# ScanseSweep_Final.net
KiCad netlist of a schematic drawn in EAGLE
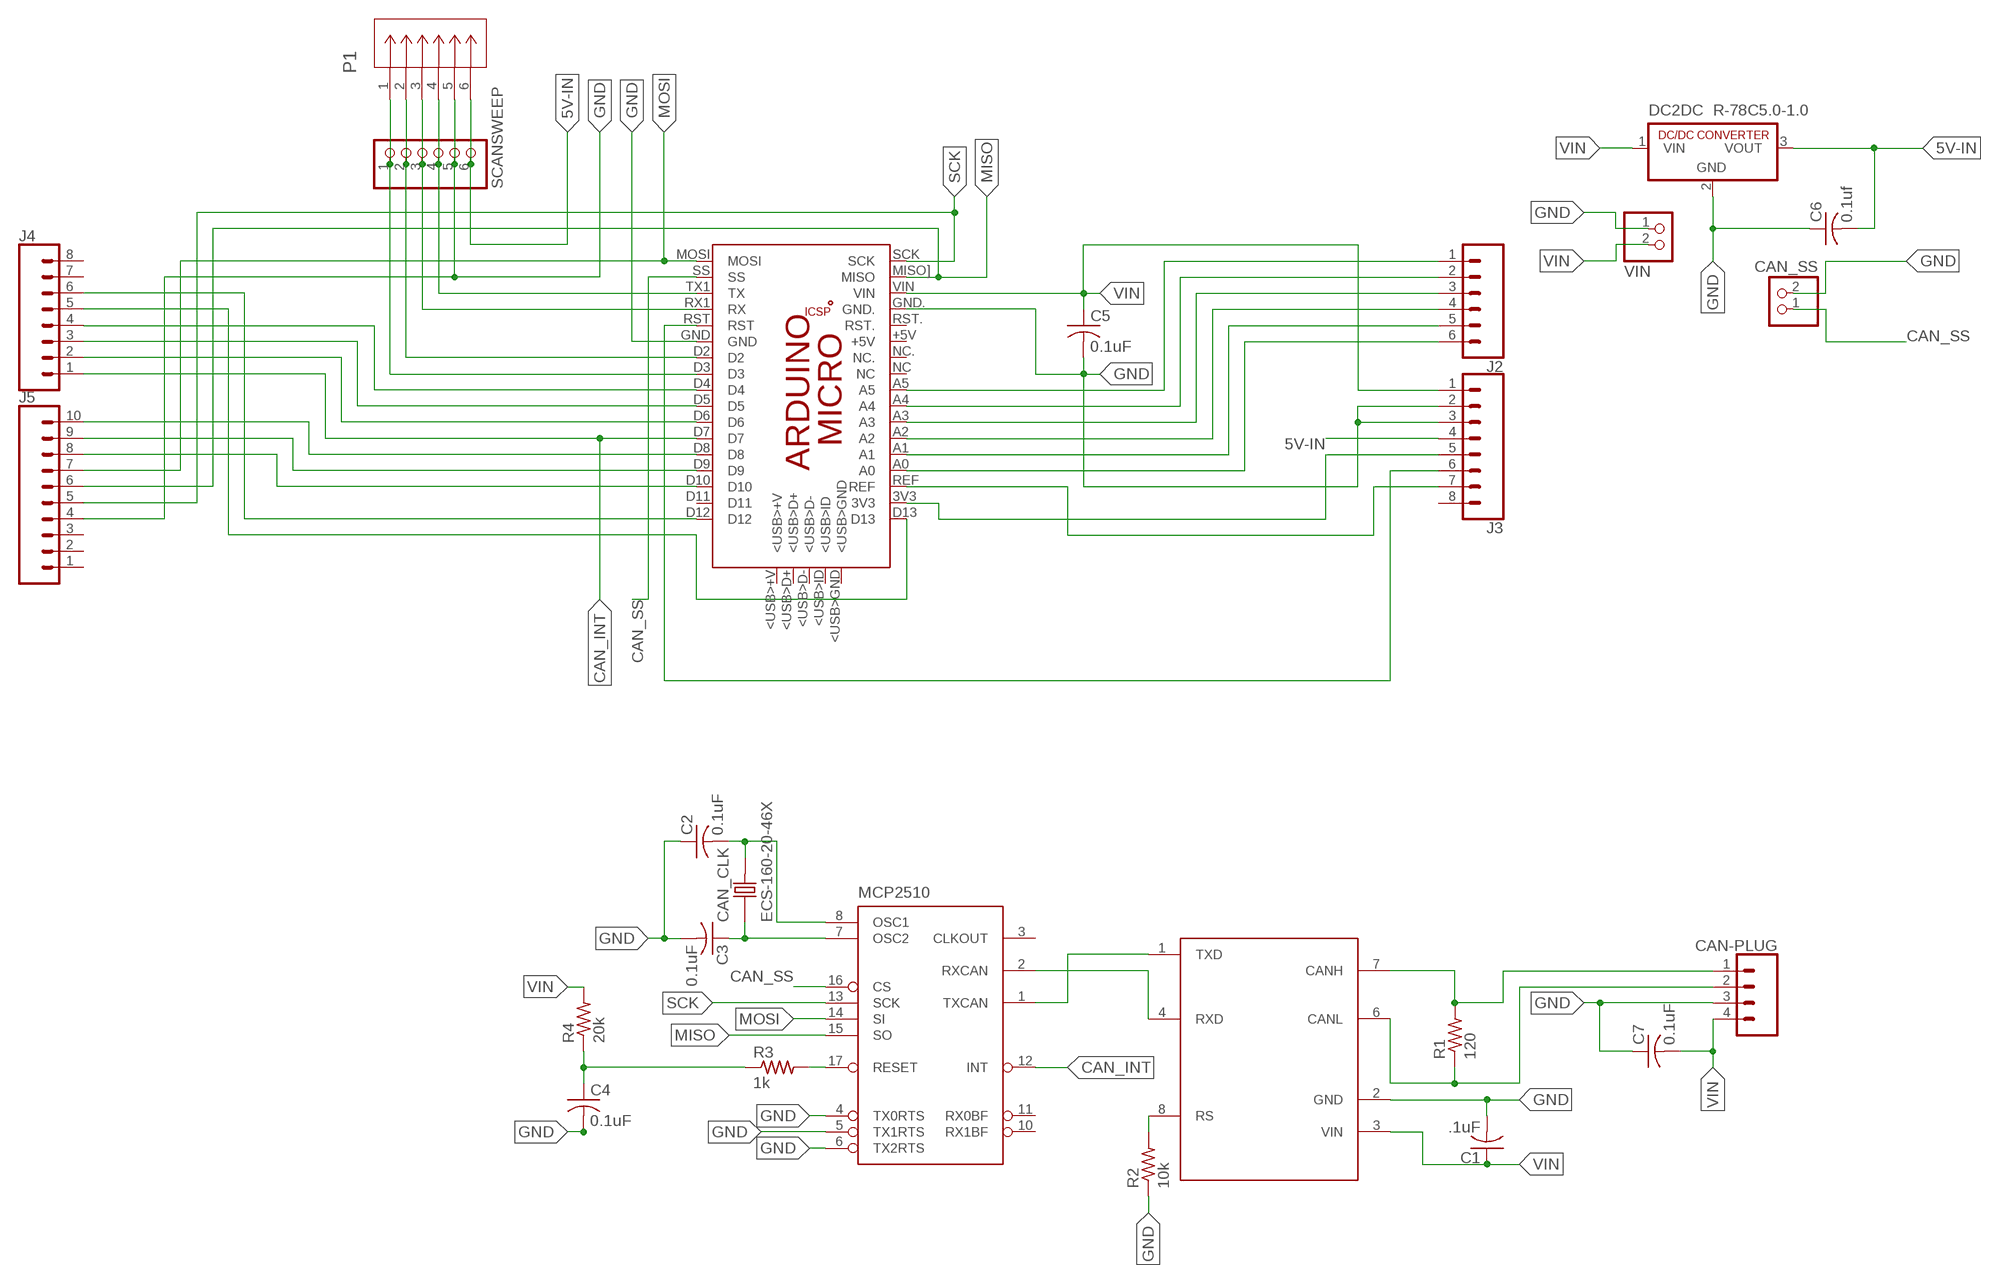
[diagram p0: schematic, sheet 1]

(export (version "E")
  (design (tool "Eeschema 10.0.6"))
  (components
    (comp (ref "C1")
      (value ".1uF")
      (footprint "eagle-import:C025-024X044")
      (libsource (lib "eagle-import") (part "C-US025-024X044"))
    )
    (comp (ref "C2")
      (value "0.1uF")
      (footprint "eagle-import:C025-024X044")
      (libsource (lib "eagle-import") (part "C-US025-024X044"))
    )
    (comp (ref "C3")
      (value "0.1uF")
      (footprint "eagle-import:C025-024X044")
      (libsource (lib "eagle-import") (part "C-US025-024X044"))
    )
    (comp (ref "C4")
      (value "0.1uF")
      (footprint "eagle-import:C025-024X044")
      (libsource (lib "eagle-import") (part "C-US025-024X044"))
    )
    (comp (ref "C5")
      (value "0.1uF")
      (footprint "eagle-import:C025-024X044")
      (libsource (lib "eagle-import") (part "C-US025-024X044"))
    )
    (comp (ref "C6")
      (value "0.1uf")
      (footprint "eagle-import:C025-024X044")
      (libsource (lib "eagle-import") (part "C-US025-024X044"))
    )
    (comp (ref "C7")
      (value "0.1uF")
      (footprint "eagle-import:C025-024X044")
      (libsource (lib "eagle-import") (part "C-US025-024X044"))
    )
    (comp (ref "CAN_CLK")
      (value "ECS-160-20-46X")
      (footprint "eagle-import:XTAL_ECS-160-20-46X")
      (fields (field (name "DIGI-KEY_PART_NUMBER") "XC1759-ND") (field (name "MF") "ECS Inc."))
      (libsource (lib "eagle-import") (part "ECS-160-20-46X"))
    )
    (comp (ref "CAN_SS_TEST")
      (value "CAN_SS")
      (footprint "eagle-import:1X02")
      (libsource (lib "eagle-import") (part "PINHD-1X2"))
    )
    (comp (ref "DC2DC")
      (value "R-78C5.0-1.0")
      (footprint "eagle-import:SIP3")
      (libsource (lib "eagle-import") (part "R-78C-1.05.0"))
    )
    (comp (ref "J1")
      (value "CAN-PLUG")
      (footprint "eagle-import:SCREWTERMINAL-3.5MM-4")
      (libsource (lib "eagle-import") (part "CONN_04SCREW"))
    )
    (comp (ref "J2")
      (value "CONN_06SILK_FEMALE_PTH")
      (footprint "eagle-import:1X06")
      (libsource (lib "eagle-import") (part "CONN_06SILK_FEMALE_PTH"))
    )
    (comp (ref "J3")
      (value "CONN_08\"")
      (footprint "eagle-import:1X08")
      (libsource (lib "eagle-import") (part "CONN_08{dblquote}"))
    )
    (comp (ref "J4")
      (value "CONN_08\"")
      (footprint "eagle-import:1X08")
      (libsource (lib "eagle-import") (part "CONN_08{dblquote}"))
    )
    (comp (ref "J5")
      (value "CONN_10\"")
      (footprint "eagle-import:1X10")
      (libsource (lib "eagle-import") (part "CONN_10{dblquote}"))
    )
    (comp (ref "MCP2510")
      (value "MCP2510P")
      (footprint "eagle-import:DIL18")
      (libsource (lib "eagle-import") (part "MCP2510P"))
    )
    (comp (ref "MCP2551")
      (value "MCP2551MCP2551")
      (footprint "eagle-import:DIL08")
      (libsource (lib "eagle-import") (part "MCP2551MCP2551"))
    )
    (comp (ref "P1")
      (value "S6B-ZR(LF)(SN)")
      (footprint "eagle-import:S6B-ZR")
      (fields (field (name "MANUFACTURER_PART_NUMBER") "S6BZRLFSN"))
      (libsource (lib "eagle-import") (part "S6B-ZR(LF)(SN)"))
    )
    (comp (ref "PCB2")
      (value "ARDUINO_MICRO")
      (footprint "eagle-import:ARDUINO_MICRO")
      (libsource (lib "eagle-import") (part "ARDUINO_MICRO"))
    )
    (comp (ref "R1")
      (value "120")
      (footprint "eagle-import:0204_5")
      (libsource (lib "eagle-import") (part "R-US_0204/5"))
    )
    (comp (ref "R2")
      (value "10k")
      (footprint "eagle-import:0204_5")
      (libsource (lib "eagle-import") (part "R-US_0204/5"))
    )
    (comp (ref "R3")
      (value "1k")
      (footprint "eagle-import:0204_5")
      (libsource (lib "eagle-import") (part "R-US_0204/5"))
    )
    (comp (ref "R4")
      (value "20k")
      (footprint "eagle-import:0204_5")
      (libsource (lib "eagle-import") (part "R-US_0204/5"))
    )
    (comp (ref "SCANSESWEEP")
      (value "SCANSWEEP")
      (footprint "eagle-import:1X06")
      (libsource (lib "eagle-import") (part "PINHD-1X6"))
    )
    (comp (ref "VIN_TEST")
      (value "VIN")
      (footprint "eagle-import:1X02")
      (libsource (lib "eagle-import") (part "PINHD-1X2"))
    )
  )
  (nets
    (net (code "1") (name "/CAN_SS") (class "Default")
      (node (ref "CAN_SS_TEST") (pin "1") (pinfunction "1_1") (pintype "passive"))
      (node (ref "MCP2510") (pin "16") (pinfunction "CS_16") (pintype "input"))
      (node (ref "PCB2") (pin "SS") (pinfunction "SS_SS") (pintype "bidirectional"))
    )
    (net (code "2") (name "5V-IN") (class "Default")
      (node (ref "C6") (pin "2") (pinfunction "2_2") (pintype "passive"))
      (node (ref "DC2DC") (pin "3") (pinfunction "VOUT_3") (pintype "passive"))
      (node (ref "J3") (pin "4") (pinfunction "4_4") (pintype "passive"))
      (node (ref "P1") (pin "6") (pinfunction "6_6") (pintype "passive"))
      (node (ref "SCANSESWEEP") (pin "6") (pinfunction "6_6") (pintype "passive"))
    )
    (net (code "3") (name "CAN_INT") (class "Default")
      (node (ref "J4") (pin "1") (pinfunction "1_1") (pintype "passive"))
      (node (ref "MCP2510") (pin "12") (pinfunction "INT_12") (pintype "output"))
      (node (ref "PCB2") (pin "D7") (pinfunction "D7_D7") (pintype "bidirectional"))
    )
    (net (code "4") (name "GND") (class "Default")
      (node (ref "C1") (pin "2") (pinfunction "2_2") (pintype "passive"))
      (node (ref "C2") (pin "1") (pinfunction "1_1") (pintype "passive"))
      (node (ref "C3") (pin "2") (pinfunction "2_2") (pintype "passive"))
      (node (ref "C4") (pin "2") (pinfunction "2_2") (pintype "passive"))
      (node (ref "C5") (pin "2") (pinfunction "2_2") (pintype "passive"))
      (node (ref "C6") (pin "1") (pinfunction "1_1") (pintype "passive"))
      (node (ref "C7") (pin "1") (pinfunction "1_1") (pintype "passive"))
      (node (ref "CAN_SS_TEST") (pin "2") (pinfunction "2_2") (pintype "passive"))
      (node (ref "DC2DC") (pin "2") (pinfunction "GND_2") (pintype "passive"))
      (node (ref "J1") (pin "3") (pinfunction "3_3") (pintype "passive"))
      (node (ref "J3") (pin "2") (pinfunction "2_2") (pintype "passive"))
      (node (ref "J3") (pin "3") (pinfunction "3_3") (pintype "passive"))
      (node (ref "J5") (pin "4") (pinfunction "4_4") (pintype "passive"))
      (node (ref "MCP2510") (pin "4") (pinfunction "TX0RTS_4") (pintype "input"))
      (node (ref "MCP2510") (pin "5") (pinfunction "TX1RTS_5") (pintype "input"))
      (node (ref "MCP2510") (pin "6") (pinfunction "TX2RTS_6") (pintype "input"))
      (node (ref "MCP2551") (pin "2") (pinfunction "GND_2") (pintype "bidirectional"))
      (node (ref "P1") (pin "5") (pinfunction "5_5") (pintype "passive"))
      (node (ref "PCB2") (pin "GND") (pinfunction "GND_GND") (pintype "bidirectional"))
      (node (ref "PCB2") (pin "GND.") (pinfunction "GND._GND.") (pintype "bidirectional"))
      (node (ref "R2") (pin "1") (pinfunction "1_1") (pintype "passive"))
      (node (ref "SCANSESWEEP") (pin "5") (pinfunction "5_5") (pintype "passive"))
      (node (ref "VIN_TEST") (pin "1") (pinfunction "1_1") (pintype "passive"))
    )
    (net (code "5") (name "MISO") (class "Default")
      (node (ref "J5") (pin "6") (pinfunction "6_6") (pintype "passive"))
      (node (ref "MCP2510") (pin "15") (pinfunction "SO_15") (pintype "output"))
      (node (ref "PCB2") (pin "MISO]") (pinfunction "MISO_MISO]") (pintype "bidirectional"))
    )
    (net (code "6") (name "MOSI") (class "Default")
      (node (ref "J5") (pin "7") (pinfunction "7_7") (pintype "passive"))
      (node (ref "MCP2510") (pin "14") (pinfunction "SI_14") (pintype "input"))
      (node (ref "PCB2") (pin "MOSI") (pinfunction "MOSI_MOSI") (pintype "bidirectional"))
    )
    (net (code "7") (name "Net-(C4-Pad1)") (class "Default")
      (node (ref "C4") (pin "1") (pinfunction "1_1") (pintype "passive"))
      (node (ref "R3") (pin "1") (pinfunction "1_1") (pintype "passive"))
      (node (ref "R4") (pin "1") (pinfunction "1_1") (pintype "passive"))
    )
    (net (code "8") (name "Net-(J2-Pad1)") (class "Default")
      (node (ref "J2") (pin "1") (pinfunction "1_1") (pintype "passive"))
      (node (ref "PCB2") (pin "A5") (pinfunction "A5_A5") (pintype "bidirectional"))
    )
    (net (code "9") (name "Net-(J2-Pad2)") (class "Default")
      (node (ref "J2") (pin "2") (pinfunction "2_2") (pintype "passive"))
      (node (ref "PCB2") (pin "A4") (pinfunction "A4_A4") (pintype "bidirectional"))
    )
    (net (code "10") (name "Net-(J2-Pad3)") (class "Default")
      (node (ref "J2") (pin "3") (pinfunction "3_3") (pintype "passive"))
      (node (ref "PCB2") (pin "A3") (pinfunction "A3_A3") (pintype "bidirectional"))
    )
    (net (code "11") (name "Net-(J2-Pad4)") (class "Default")
      (node (ref "J2") (pin "4") (pinfunction "4_4") (pintype "passive"))
      (node (ref "PCB2") (pin "A2") (pinfunction "A2_A2") (pintype "bidirectional"))
    )
    (net (code "12") (name "Net-(J2-Pad5)") (class "Default")
      (node (ref "J2") (pin "5") (pinfunction "5_5") (pintype "passive"))
      (node (ref "PCB2") (pin "A1") (pinfunction "A1_A1") (pintype "bidirectional"))
    )
    (net (code "13") (name "Net-(J2-Pad6)") (class "Default")
      (node (ref "J2") (pin "6") (pinfunction "6_6") (pintype "passive"))
      (node (ref "PCB2") (pin "A0") (pinfunction "A0_A0") (pintype "bidirectional"))
    )
    (net (code "14") (name "Net-(J3-Pad5)") (class "Default")
      (node (ref "J3") (pin "5") (pinfunction "5_5") (pintype "passive"))
      (node (ref "PCB2") (pin "3V3") (pinfunction "3V3_3V3") (pintype "bidirectional"))
    )
    (net (code "15") (name "Net-(J3-Pad6)") (class "Default")
      (node (ref "J3") (pin "6") (pinfunction "6_6") (pintype "passive"))
      (node (ref "PCB2") (pin "RST") (pinfunction "RST_RST") (pintype "bidirectional"))
    )
    (net (code "16") (name "Net-(J3-Pad7)") (class "Default")
      (node (ref "J3") (pin "7") (pinfunction "7_7") (pintype "passive"))
      (node (ref "PCB2") (pin "REF") (pinfunction "REF_REF") (pintype "bidirectional"))
    )
    (net (code "17") (name "Net-(J4-Pad2)") (class "Default")
      (node (ref "J4") (pin "2") (pinfunction "2_2") (pintype "passive"))
      (node (ref "PCB2") (pin "D6") (pinfunction "D6_D6") (pintype "bidirectional"))
    )
    (net (code "18") (name "Net-(J4-Pad3)") (class "Default")
      (node (ref "J4") (pin "3") (pinfunction "3_3") (pintype "passive"))
      (node (ref "PCB2") (pin "D5") (pinfunction "D5_D5") (pintype "bidirectional"))
    )
    (net (code "19") (name "Net-(J4-Pad4)") (class "Default")
      (node (ref "J4") (pin "4") (pinfunction "4_4") (pintype "passive"))
      (node (ref "PCB2") (pin "D4") (pinfunction "D4_D4") (pintype "bidirectional"))
    )
    (net (code "20") (name "Net-(J4-Pad5)") (class "Default")
      (node (ref "J4") (pin "5") (pinfunction "5_5") (pintype "passive"))
      (node (ref "PCB2") (pin "D13") (pinfunction "D13_D13") (pintype "bidirectional"))
    )
    (net (code "21") (name "Net-(J4-Pad6)") (class "Default")
      (node (ref "J4") (pin "6") (pinfunction "6_6") (pintype "passive"))
      (node (ref "PCB2") (pin "D12") (pinfunction "D12_D12") (pintype "bidirectional"))
    )
    (net (code "22") (name "Net-(J5-Pad8)") (class "Default")
      (node (ref "J5") (pin "8") (pinfunction "8_8") (pintype "passive"))
      (node (ref "PCB2") (pin "D10") (pinfunction "D10_D10") (pintype "bidirectional"))
    )
    (net (code "23") (name "Net-(J5-Pad9)") (class "Default")
      (node (ref "J5") (pin "9") (pinfunction "9_9") (pintype "passive"))
      (node (ref "PCB2") (pin "D9") (pinfunction "D9_D9") (pintype "bidirectional"))
    )
    (net (code "24") (name "Net-(J5-Pad10)") (class "Default")
      (node (ref "J5") (pin "10") (pinfunction "10_10") (pintype "passive"))
      (node (ref "PCB2") (pin "D8") (pinfunction "D8_D8") (pintype "bidirectional"))
    )
    (net (code "25") (name "Net-(MCP2510A-OSC1)") (class "Default")
      (node (ref "C2") (pin "2") (pinfunction "2_2") (pintype "passive"))
      (node (ref "CAN_CLK") (pin "2") (pinfunction "2_2") (pintype "passive"))
      (node (ref "MCP2510") (pin "8") (pinfunction "OSC1_8") (pintype "input"))
    )
    (net (code "26") (name "Net-(MCP2510A-OSC2)") (class "Default")
      (node (ref "C3") (pin "1") (pinfunction "1_1") (pintype "passive"))
      (node (ref "CAN_CLK") (pin "1") (pinfunction "1_1") (pintype "passive"))
      (node (ref "MCP2510") (pin "7") (pinfunction "OSC2_7") (pintype "output"))
    )
    (net (code "27") (name "Net-(MCP2510A-RESET)") (class "Default")
      (node (ref "MCP2510") (pin "17") (pinfunction "RESET_17") (pintype "input"))
      (node (ref "R3") (pin "2") (pinfunction "2_2") (pintype "passive"))
    )
    (net (code "28") (name "Net-(MCP2510A-RXCAN)") (class "Default")
      (node (ref "MCP2510") (pin "2") (pinfunction "RXCAN_2") (pintype "input"))
      (node (ref "MCP2551") (pin "4") (pinfunction "RXD_4") (pintype "bidirectional"))
    )
    (net (code "29") (name "Net-(MCP2510A-TXCAN)") (class "Default")
      (node (ref "MCP2510") (pin "1") (pinfunction "TXCAN_1") (pintype "output"))
      (node (ref "MCP2551") (pin "1") (pinfunction "TXD_1") (pintype "bidirectional"))
    )
    (net (code "30") (name "Net-(MCP2551-CANH)") (class "Default")
      (node (ref "J1") (pin "1") (pinfunction "1_1") (pintype "passive"))
      (node (ref "MCP2551") (pin "7") (pinfunction "CANH_7") (pintype "bidirectional"))
      (node (ref "R1") (pin "2") (pinfunction "2_2") (pintype "passive"))
    )
    (net (code "31") (name "Net-(MCP2551-CANL)") (class "Default")
      (node (ref "J1") (pin "2") (pinfunction "2_2") (pintype "passive"))
      (node (ref "MCP2551") (pin "6") (pinfunction "CANL_6") (pintype "bidirectional"))
      (node (ref "R1") (pin "1") (pinfunction "1_1") (pintype "passive"))
    )
    (net (code "32") (name "Net-(MCP2551-RS)") (class "Default")
      (node (ref "MCP2551") (pin "8") (pinfunction "RS_8") (pintype "bidirectional"))
      (node (ref "R2") (pin "2") (pinfunction "2_2") (pintype "passive"))
    )
    (net (code "33") (name "Net-(P1-Pad1)") (class "Default")
      (node (ref "P1") (pin "1") (pinfunction "1_1") (pintype "passive"))
      (node (ref "PCB2") (pin "D3") (pinfunction "D3_D3") (pintype "bidirectional"))
      (node (ref "SCANSESWEEP") (pin "1") (pinfunction "1_1") (pintype "passive"))
    )
    (net (code "34") (name "Net-(P1-Pad2)") (class "Default")
      (node (ref "P1") (pin "2") (pinfunction "2_2") (pintype "passive"))
      (node (ref "PCB2") (pin "D2") (pinfunction "D2_D2") (pintype "bidirectional"))
      (node (ref "SCANSESWEEP") (pin "2") (pinfunction "2_2") (pintype "passive"))
    )
    (net (code "35") (name "Net-(PCB2-RX)") (class "Default")
      (node (ref "P1") (pin "3") (pinfunction "3_3") (pintype "passive"))
      (node (ref "PCB2") (pin "RX1") (pinfunction "RX_RX1") (pintype "bidirectional"))
      (node (ref "SCANSESWEEP") (pin "3") (pinfunction "3_3") (pintype "passive"))
    )
    (net (code "36") (name "Net-(PCB2-TX)") (class "Default")
      (node (ref "P1") (pin "4") (pinfunction "4_4") (pintype "passive"))
      (node (ref "PCB2") (pin "TX1") (pinfunction "TX_TX1") (pintype "bidirectional"))
      (node (ref "SCANSESWEEP") (pin "4") (pinfunction "4_4") (pintype "passive"))
    )
    (net (code "37") (name "SCK") (class "Default")
      (node (ref "J5") (pin "5") (pinfunction "5_5") (pintype "passive"))
      (node (ref "MCP2510") (pin "13") (pinfunction "SCK_13") (pintype "input"))
      (node (ref "PCB2") (pin "SCK") (pinfunction "SCK_SCK") (pintype "bidirectional"))
    )
    (net (code "38") (name "VIN") (class "Default")
      (node (ref "C1") (pin "1") (pinfunction "1_1") (pintype "passive"))
      (node (ref "C5") (pin "1") (pinfunction "1_1") (pintype "passive"))
      (node (ref "C7") (pin "2") (pinfunction "2_2") (pintype "passive"))
      (node (ref "DC2DC") (pin "1") (pinfunction "VIN_1") (pintype "passive"))
      (node (ref "J1") (pin "4") (pinfunction "4_4") (pintype "passive"))
      (node (ref "J3") (pin "1") (pinfunction "1_1") (pintype "passive"))
      (node (ref "MCP2551") (pin "3") (pinfunction "VIN_3") (pintype "bidirectional"))
      (node (ref "PCB2") (pin "VIN") (pinfunction "VIN_VIN") (pintype "bidirectional"))
      (node (ref "R4") (pin "2") (pinfunction "2_2") (pintype "passive"))
      (node (ref "VIN_TEST") (pin "2") (pinfunction "2_2") (pintype "passive"))
    )
    (net (code "39") (name "unconnected-(J3-Pad8)") (class "Default")
      (node (ref "J3") (pin "8") (pinfunction "8_8") (pintype "passive"))
    )
    (net (code "40") (name "unconnected-(J4-Pad7)") (class "Default")
      (node (ref "J4") (pin "7") (pinfunction "7_7") (pintype "passive"))
    )
    (net (code "41") (name "unconnected-(J4-Pad8)") (class "Default")
      (node (ref "J4") (pin "8") (pinfunction "8_8") (pintype "passive"))
    )
    (net (code "42") (name "unconnected-(J5-Pad1)") (class "Default")
      (node (ref "J5") (pin "1") (pinfunction "1_1") (pintype "passive"))
    )
    (net (code "43") (name "unconnected-(J5-Pad2)") (class "Default")
      (node (ref "J5") (pin "2") (pinfunction "2_2") (pintype "passive"))
    )
    (net (code "44") (name "unconnected-(J5-Pad3)") (class "Default")
      (node (ref "J5") (pin "3") (pinfunction "3_3") (pintype "passive"))
    )
    (net (code "45") (name "unconnected-(MCP2510A-CLKOUT-Pad3)") (class "Default")
      (node (ref "MCP2510") (pin "3") (pinfunction "CLKOUT_3") (pintype "output"))
    )
    (net (code "46") (name "unconnected-(MCP2510A-RX0BF-Pad11)") (class "Default")
      (node (ref "MCP2510") (pin "11") (pinfunction "RX0BF_11") (pintype "output"))
    )
    (net (code "47") (name "unconnected-(MCP2510A-RX1BF-Pad10)") (class "Default")
      (node (ref "MCP2510") (pin "10") (pinfunction "RX1BF_10") (pintype "output"))
    )
    (net (code "48") (name "unconnected-(PCB2-Pad+5V)") (class "Default")
      (node (ref "PCB2") (pin "+5V") (pinfunction "+5V_+5V") (pintype "bidirectional"))
    )
    (net (code "49") (name "unconnected-(PCB2-Pad5V)") (class "Default")
      (node (ref "PCB2") (pin "5V") (pinfunction "5V_5V") (pintype "bidirectional"))
    )
    (net (code "50") (name "unconnected-(PCB2-Pad<USB>+V)") (class "Default")
      (node (ref "PCB2") (pin "<USB>+V") (pinfunction "<USB>+V_<USB>+V") (pintype "bidirectional"))
    )
    (net (code "51") (name "unconnected-(PCB2-Pad<USB>D+)") (class "Default")
      (node (ref "PCB2") (pin "<USB>D+") (pinfunction "<USB>D+_<USB>D+") (pintype "bidirectional"))
    )
    (net (code "52") (name "unconnected-(PCB2-Pad<USB>D-)") (class "Default")
      (node (ref "PCB2") (pin "<USB>D-") (pinfunction "<USB>D-_<USB>D-") (pintype "bidirectional"))
    )
    (net (code "53") (name "unconnected-(PCB2-Pad<USB>GND)") (class "Default")
      (node (ref "PCB2") (pin "<USB>GND") (pinfunction "<USB>GND_<USB>GND") (pintype "bidirectional"))
    )
    (net (code "54") (name "unconnected-(PCB2-Pad<USB>ID)") (class "Default")
      (node (ref "PCB2") (pin "<USB>ID") (pinfunction "<USB>ID_<USB>ID") (pintype "bidirectional"))
    )
    (net (code "55") (name "unconnected-(PCB2-PadD11)") (class "Default")
      (node (ref "PCB2") (pin "D11") (pinfunction "D11_D11") (pintype "bidirectional"))
    )
    (net (code "56") (name "unconnected-(PCB2-PadGND_)") (class "Default")
      (node (ref "PCB2") (pin "GND_") (pinfunction "GND__GND_") (pintype "bidirectional"))
    )
    (net (code "57") (name "unconnected-(PCB2-PadMISO.)") (class "Default")
      (node (ref "PCB2") (pin "MISO.") (pinfunction "MISO._MISO.") (pintype "bidirectional"))
    )
    (net (code "58") (name "unconnected-(PCB2-PadMOSI.)") (class "Default")
      (node (ref "PCB2") (pin "MOSI.") (pinfunction "MOSI._MOSI.") (pintype "bidirectional"))
    )
    (net (code "59") (name "unconnected-(PCB2-PadNC)") (class "Default")
      (node (ref "PCB2") (pin "NC") (pinfunction "NC_NC") (pintype "bidirectional"))
    )
    (net (code "60") (name "unconnected-(PCB2-PadNC.)") (class "Default")
      (node (ref "PCB2") (pin "NC.") (pinfunction "NC._NC.") (pintype "bidirectional"))
    )
    (net (code "61") (name "unconnected-(PCB2-PadRESET..)") (class "Default")
      (node (ref "PCB2") (pin "RESET..") (pinfunction "RESET.._RESET..") (pintype "bidirectional"))
    )
    (net (code "62") (name "unconnected-(PCB2-PadRST.)") (class "Default")
      (node (ref "PCB2") (pin "RST.") (pinfunction "RST._RST.") (pintype "bidirectional"))
    )
    (net (code "63") (name "unconnected-(PCB2-PadSCK.)") (class "Default")
      (node (ref "PCB2") (pin "SCK.") (pinfunction "SCK._SCK.") (pintype "bidirectional"))
    )
  )
)
